# I2C.net
KiCad netlist of a schematic drawn in EAGLE
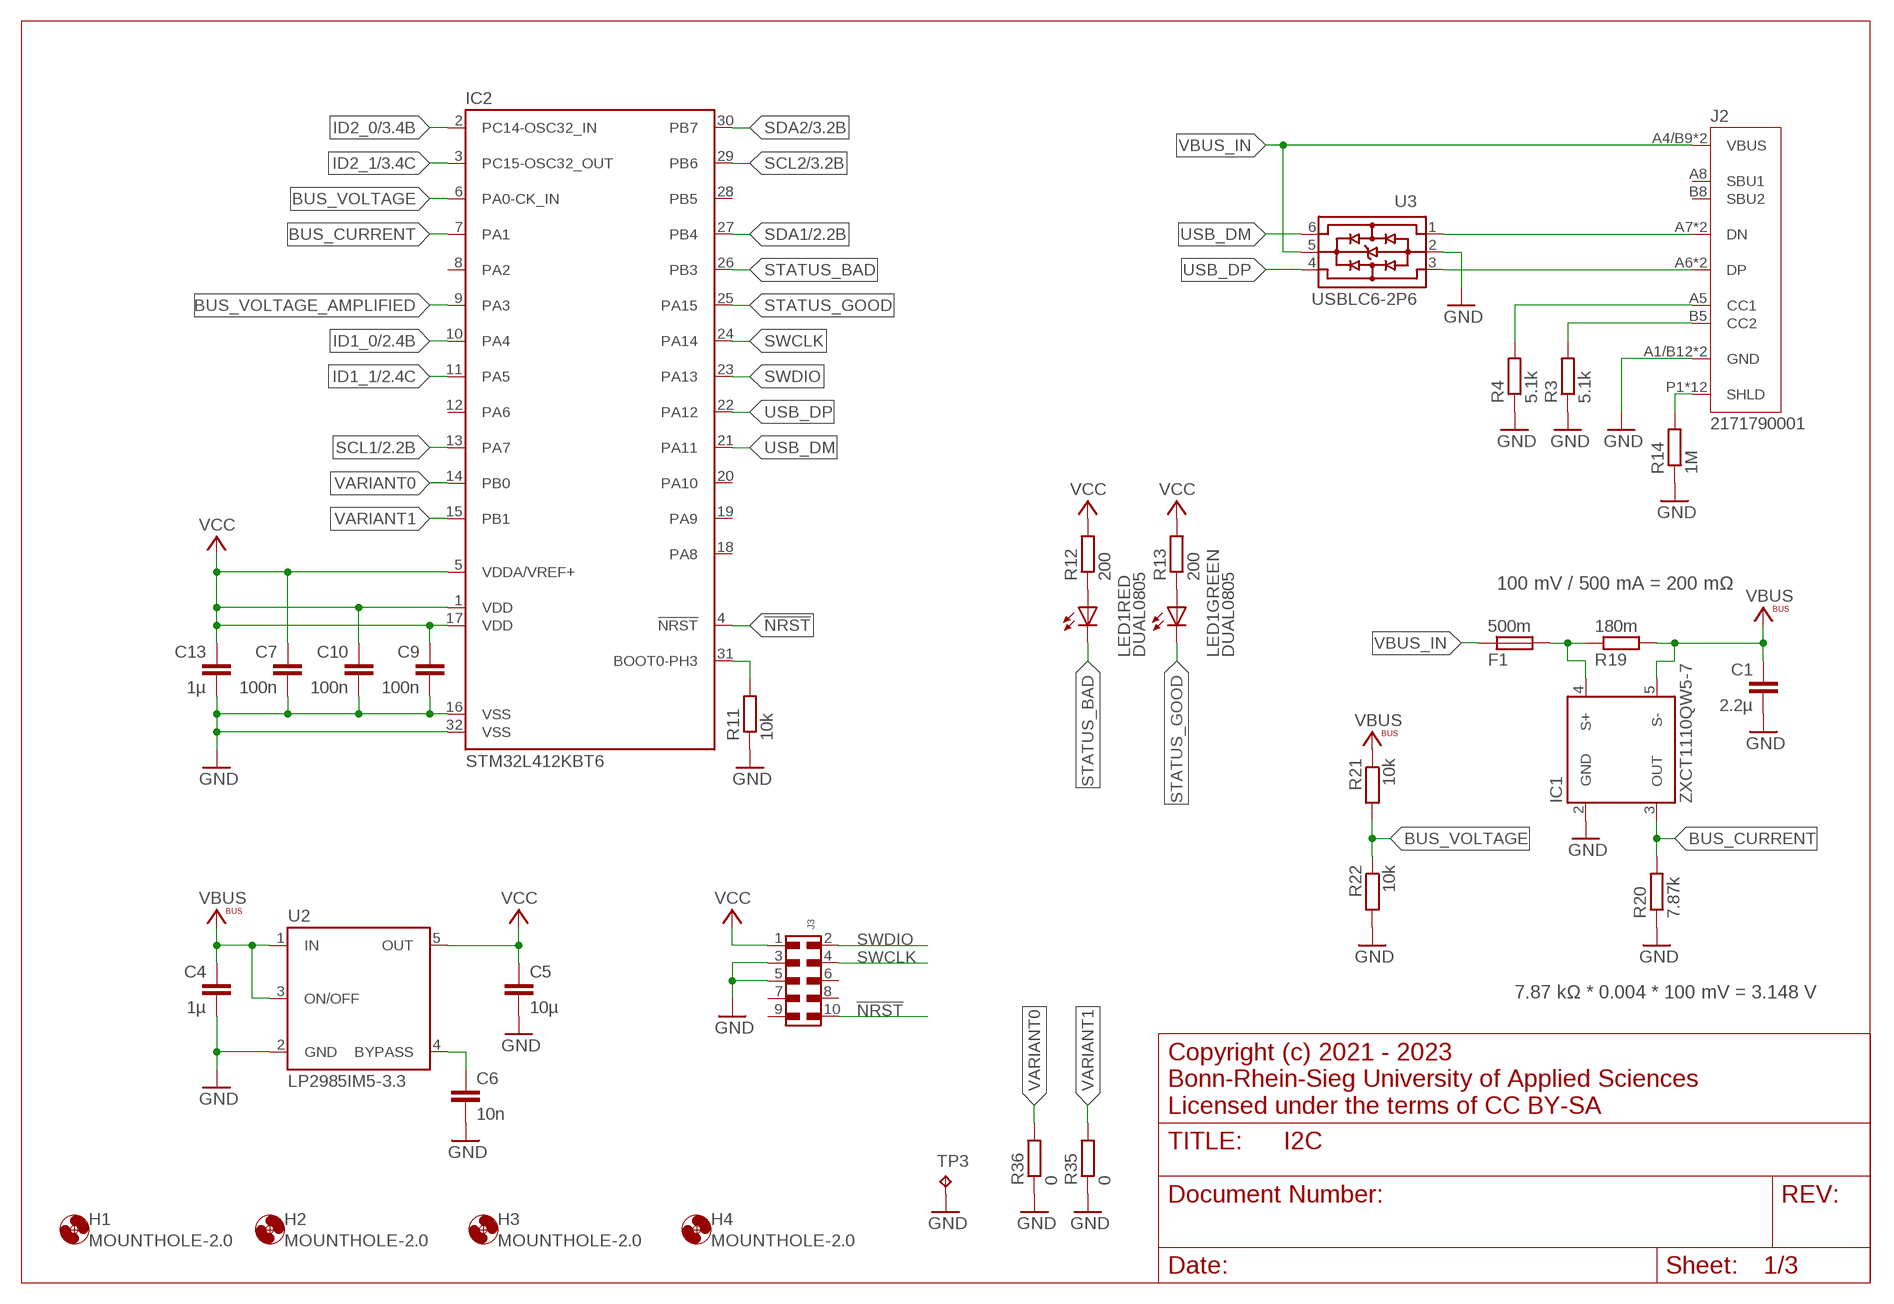
[diagram p0: schematic, sheet 1]
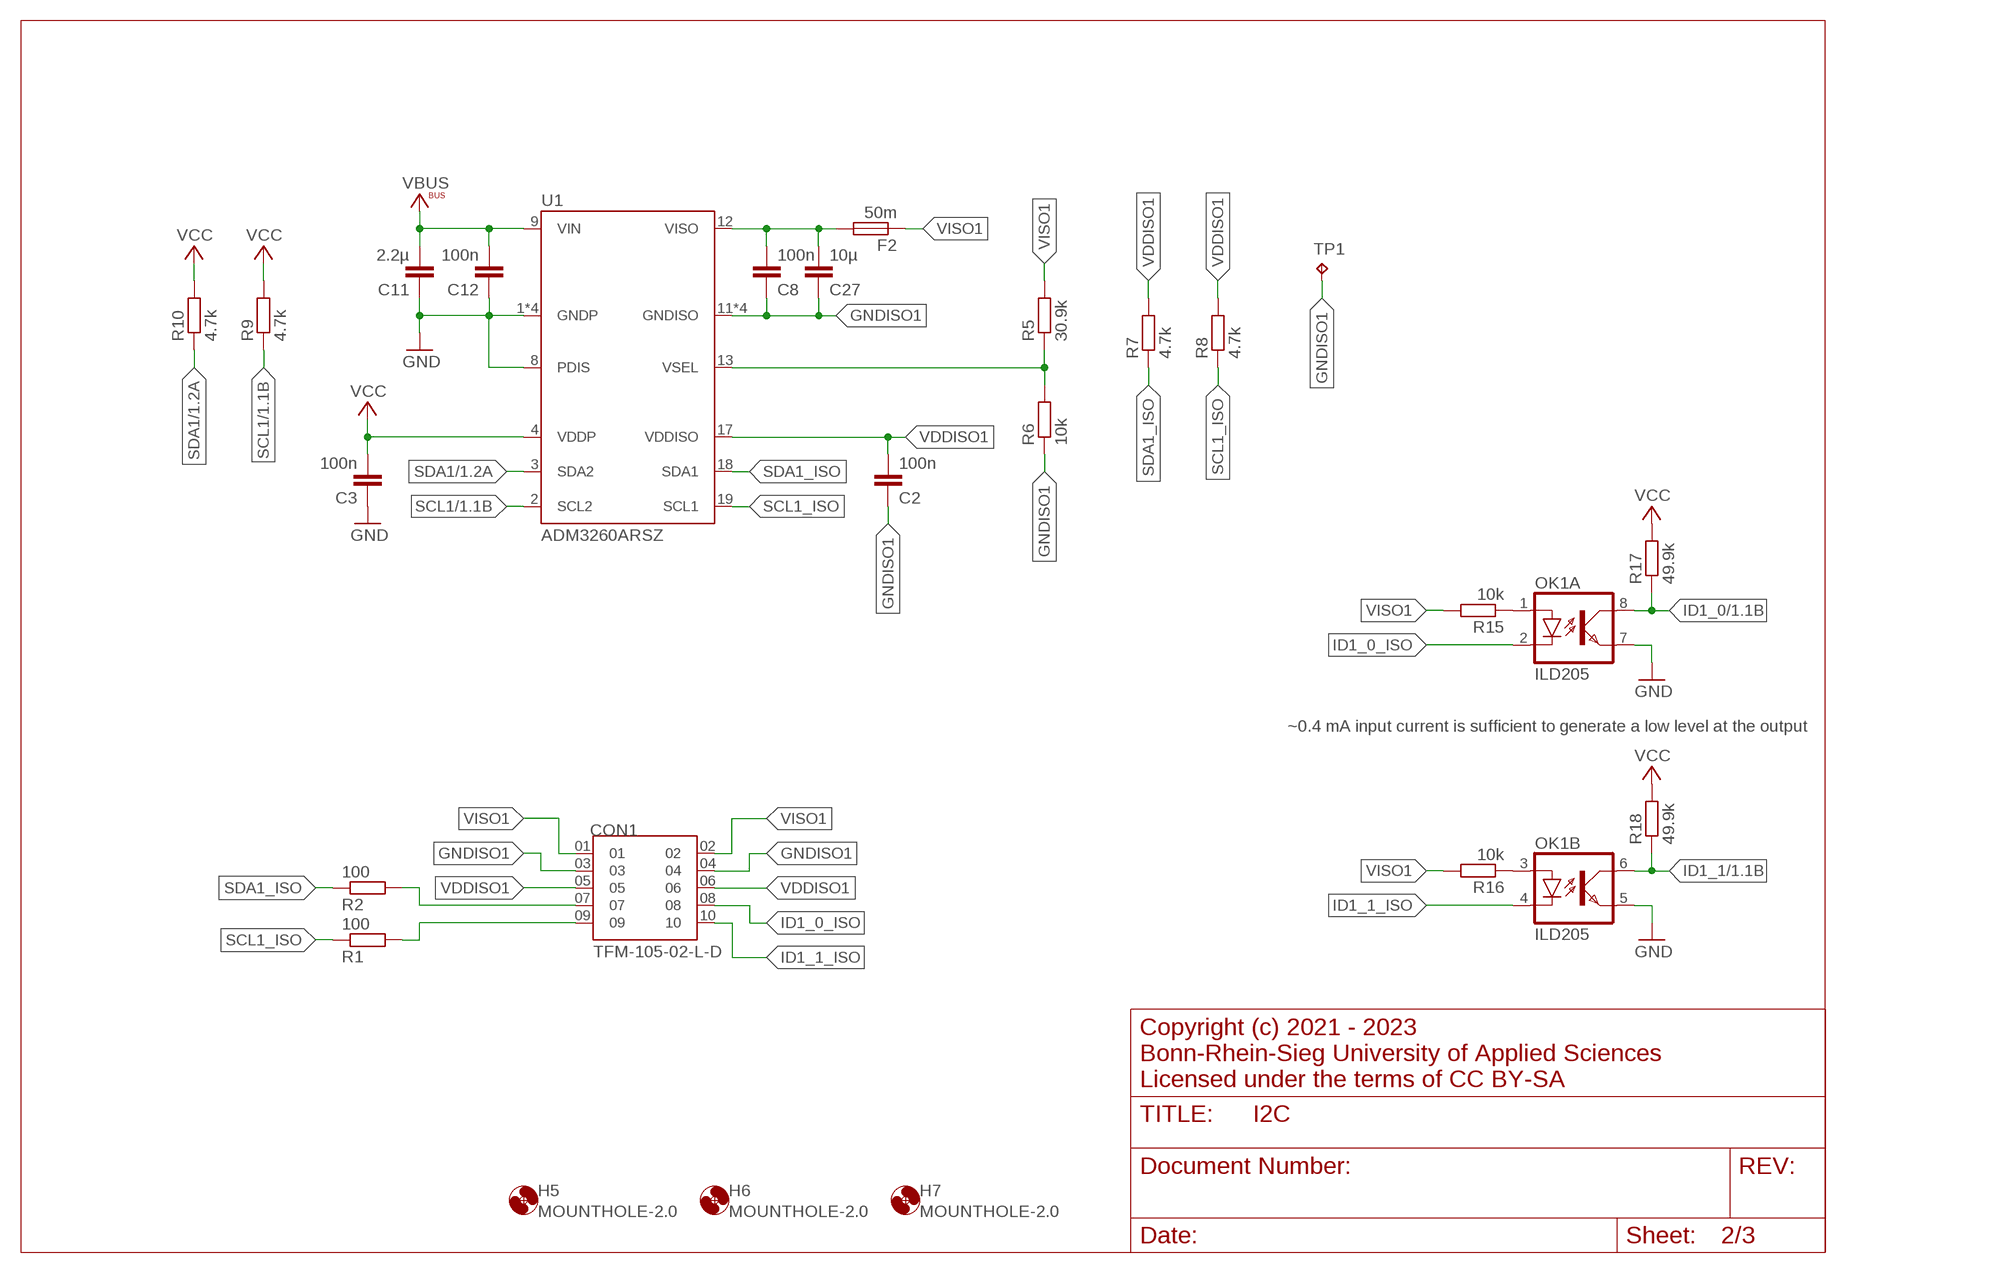
[diagram p1: schematic, sheet 2]
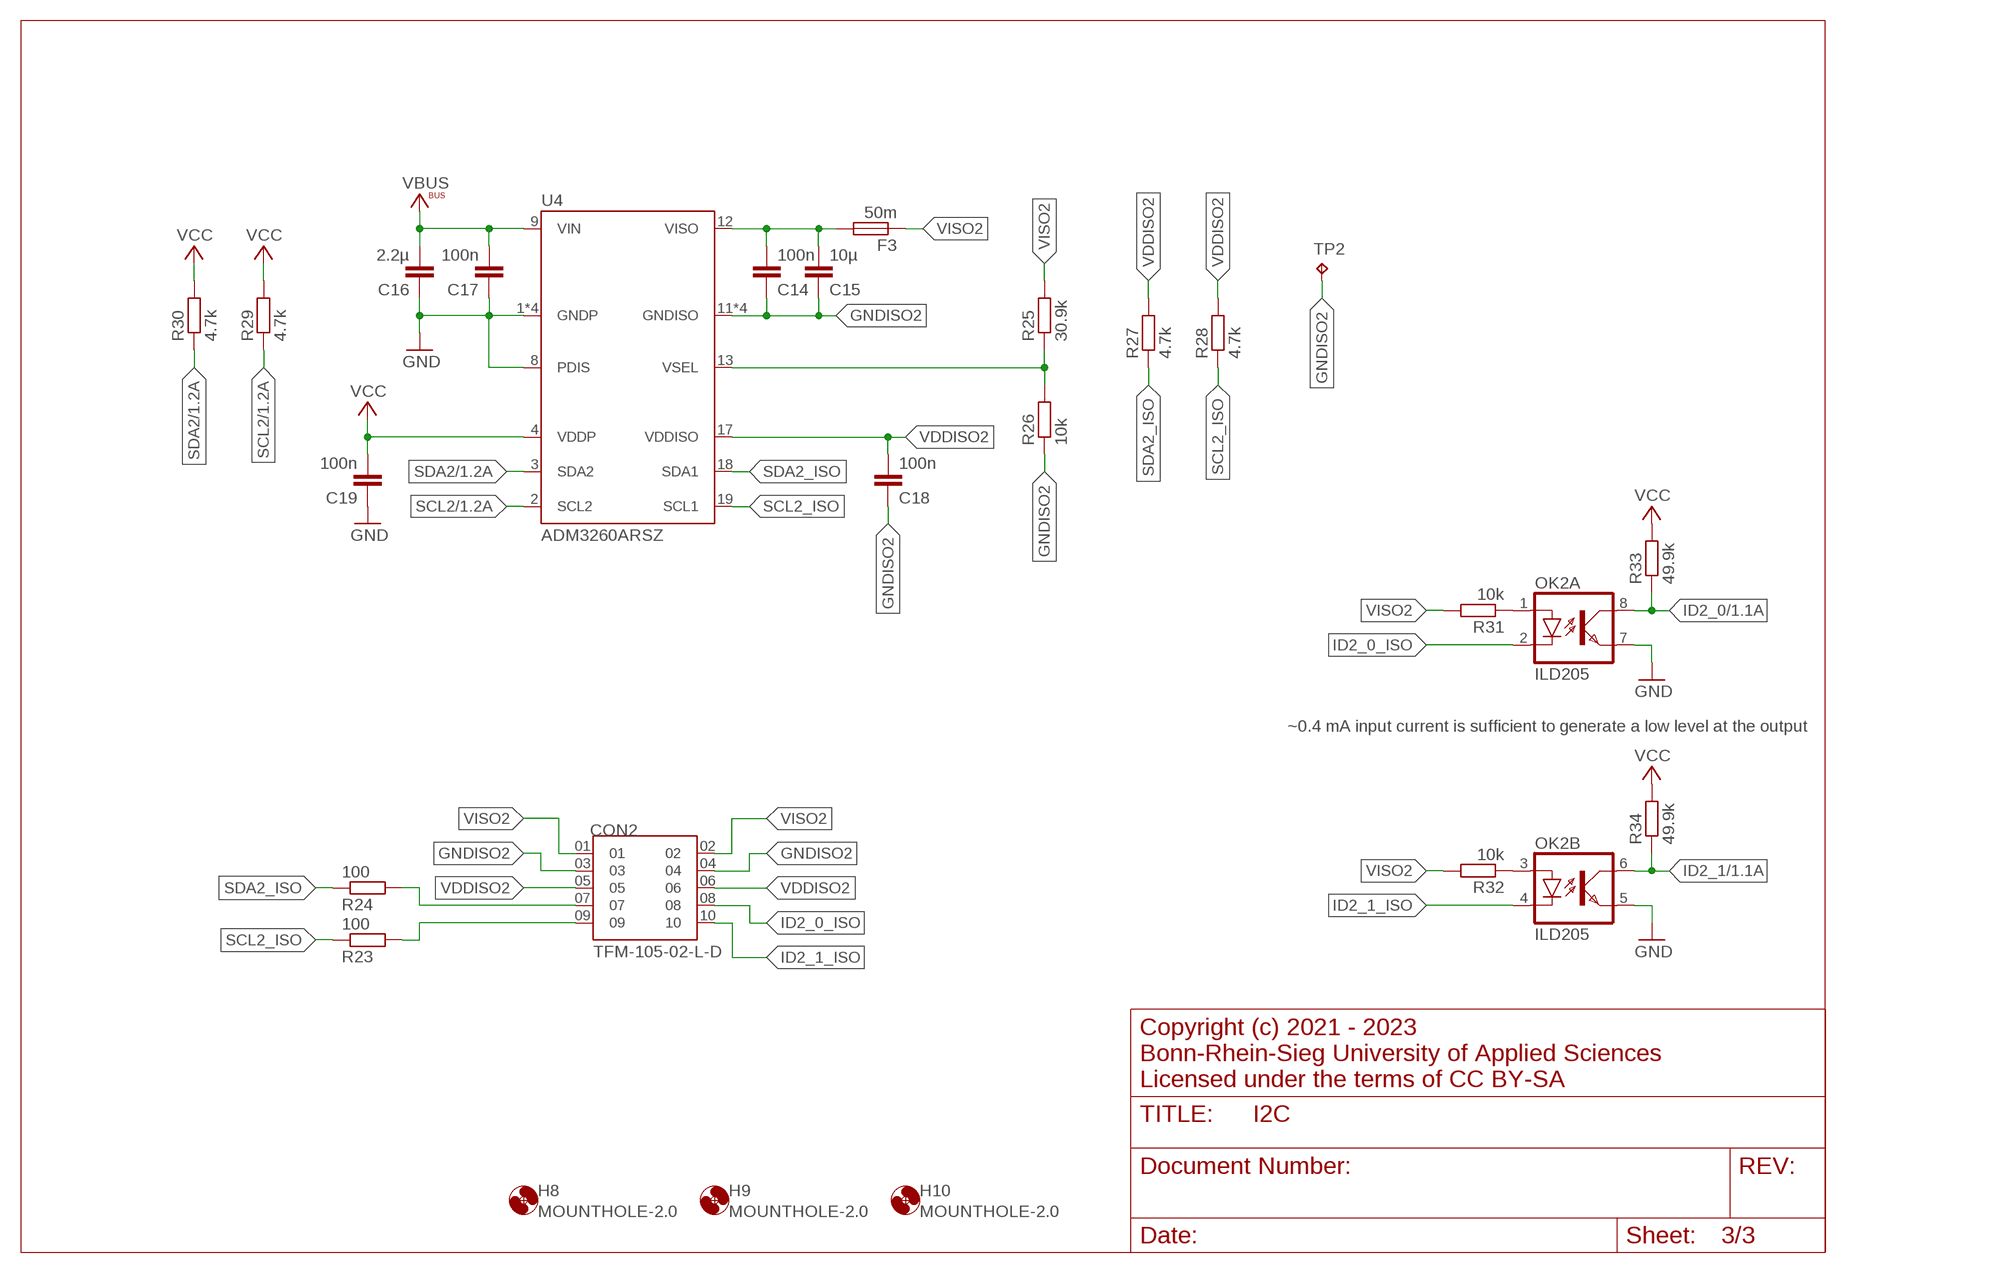
[diagram p2: schematic, sheet 3]

(export (version "E")
  (design (tool "Eeschema 10.0.6"))
  (components
    (comp (ref "C2")
      (value "100n")
      (footprint "eagle-import:C0603")
      (libsource (lib "eagle-import") (part "C-EUC0603"))
    )
    (comp (ref "C3")
      (value "100n")
      (footprint "eagle-import:C0603")
      (libsource (lib "eagle-import") (part "C-EUC0603"))
    )
    (comp (ref "C8")
      (value "100n")
      (footprint "eagle-import:C0603")
      (libsource (lib "eagle-import") (part "C-EUC0603"))
    )
    (comp (ref "C11")
      (value "2.2µ")
      (footprint "eagle-import:C0603")
      (libsource (lib "eagle-import") (part "C-EUC0603"))
    )
    (comp (ref "C12")
      (value "100n")
      (footprint "eagle-import:C0603")
      (libsource (lib "eagle-import") (part "C-EUC0603"))
    )
    (comp (ref "C27")
      (value "10µ")
      (footprint "eagle-import:C0603")
      (libsource (lib "eagle-import") (part "C-EUC0603"))
    )
    (comp (ref "CON1")
      (value "TFM-105-02-L-D")
      (footprint "eagle-import:SAMTEC_TFM-105-02-L-D")
      (libsource (lib "eagle-import") (part "TFM-105-02-L-D"))
    )
    (comp (ref "F2")
      (value "50m")
      (footprint "eagle-import:R0603")
      (libsource (lib "eagle-import") (part "FUSE0603"))
    )
    (comp (ref "H5")
      (value "MOUNTHOLE-2.0")
      (footprint "eagle-import:2.0")
      (libsource (lib "eagle-import") (part "MOUNTHOLE-2.0"))
    )
    (comp (ref "H6")
      (value "MOUNTHOLE-2.0")
      (footprint "eagle-import:2.0")
      (libsource (lib "eagle-import") (part "MOUNTHOLE-2.0"))
    )
    (comp (ref "H7")
      (value "MOUNTHOLE-2.0")
      (footprint "eagle-import:2.0")
      (libsource (lib "eagle-import") (part "MOUNTHOLE-2.0"))
    )
    (comp (ref "OK1")
      (value "ILD205")
      (footprint "eagle-import:SOIC08")
      (fields (field (name "MF") "VISHAY/TELEFUNKEN") (field (name "MPN") "ILD205T"))
      (libsource (lib "eagle-import") (part "ILD205"))
    )
    (comp (ref "R1")
      (value "100")
      (footprint "eagle-import:R0603")
      (libsource (lib "eagle-import") (part "rcl_334_R-EU_R0603"))
    )
    (comp (ref "R2")
      (value "100")
      (footprint "eagle-import:R0603")
      (libsource (lib "eagle-import") (part "rcl_334_R-EU_R0603"))
    )
    (comp (ref "R5")
      (value "30.9k")
      (footprint "eagle-import:R0603")
      (libsource (lib "eagle-import") (part "rcl_334_R-EU_R0603"))
    )
    (comp (ref "R6")
      (value "10k")
      (footprint "eagle-import:R0603")
      (libsource (lib "eagle-import") (part "rcl_334_R-EU_R0603"))
    )
    (comp (ref "R7")
      (value "4.7k")
      (footprint "eagle-import:R0603")
      (libsource (lib "eagle-import") (part "rcl_334_R-EU_R0603"))
    )
    (comp (ref "R8")
      (value "4.7k")
      (footprint "eagle-import:R0603")
      (libsource (lib "eagle-import") (part "rcl_334_R-EU_R0603"))
    )
    (comp (ref "R9")
      (value "4.7k")
      (footprint "eagle-import:R0603")
      (libsource (lib "eagle-import") (part "rcl_334_R-EU_R0603"))
    )
    (comp (ref "R10")
      (value "4.7k")
      (footprint "eagle-import:R0603")
      (libsource (lib "eagle-import") (part "rcl_334_R-EU_R0603"))
    )
    (comp (ref "R15")
      (value "10k")
      (footprint "eagle-import:R0603")
      (libsource (lib "eagle-import") (part "rcl_334_R-EU_R0603"))
    )
    (comp (ref "R16")
      (value "10k")
      (footprint "eagle-import:R0603")
      (libsource (lib "eagle-import") (part "rcl_334_R-EU_R0603"))
    )
    (comp (ref "R17")
      (value "49.9k")
      (footprint "eagle-import:R0603")
      (libsource (lib "eagle-import") (part "rcl_334_R-EU_R0603"))
    )
    (comp (ref "R18")
      (value "49.9k")
      (footprint "eagle-import:R0603")
      (libsource (lib "eagle-import") (part "rcl_334_R-EU_R0603"))
    )
    (comp (ref "TP1")
      (value "TP3.8X2.03")
      (footprint "eagle-import:3.8X2.03")
      (libsource (lib "eagle-import") (part "TP3.8X2.03"))
    )
    (comp (ref "U1")
      (value "ADM3260ARSZ")
      (footprint "eagle-import:SSOP20")
      (libsource (lib "eagle-import") (part "ADM3260RSZA"))
    )
    (comp (ref "C14")
      (value "100n")
      (footprint "eagle-import:C0603")
      (libsource (lib "eagle-import") (part "C-EUC0603"))
    )
    (comp (ref "C15")
      (value "10µ")
      (footprint "eagle-import:C0603")
      (libsource (lib "eagle-import") (part "C-EUC0603"))
    )
    (comp (ref "C16")
      (value "2.2µ")
      (footprint "eagle-import:C0603")
      (libsource (lib "eagle-import") (part "C-EUC0603"))
    )
    (comp (ref "C17")
      (value "100n")
      (footprint "eagle-import:C0603")
      (libsource (lib "eagle-import") (part "C-EUC0603"))
    )
    (comp (ref "C18")
      (value "100n")
      (footprint "eagle-import:C0603")
      (libsource (lib "eagle-import") (part "C-EUC0603"))
    )
    (comp (ref "C19")
      (value "100n")
      (footprint "eagle-import:C0603")
      (libsource (lib "eagle-import") (part "C-EUC0603"))
    )
    (comp (ref "CON2")
      (value "TFM-105-02-L-D")
      (footprint "eagle-import:SAMTEC_TFM-105-02-L-D")
      (libsource (lib "eagle-import") (part "TFM-105-02-L-D"))
    )
    (comp (ref "F3")
      (value "50m")
      (footprint "eagle-import:R0603")
      (libsource (lib "eagle-import") (part "FUSE0603"))
    )
    (comp (ref "H8")
      (value "MOUNTHOLE-2.0")
      (footprint "eagle-import:2.0")
      (libsource (lib "eagle-import") (part "MOUNTHOLE-2.0"))
    )
    (comp (ref "H9")
      (value "MOUNTHOLE-2.0")
      (footprint "eagle-import:2.0")
      (libsource (lib "eagle-import") (part "MOUNTHOLE-2.0"))
    )
    (comp (ref "H10")
      (value "MOUNTHOLE-2.0")
      (footprint "eagle-import:2.0")
      (libsource (lib "eagle-import") (part "MOUNTHOLE-2.0"))
    )
    (comp (ref "OK2")
      (value "ILD205")
      (footprint "eagle-import:SOIC08")
      (fields (field (name "MF") "VISHAY/TELEFUNKEN") (field (name "MPN") "ILD205T"))
      (libsource (lib "eagle-import") (part "ILD205"))
    )
    (comp (ref "R23")
      (value "100")
      (footprint "eagle-import:R0603")
      (libsource (lib "eagle-import") (part "rcl_334_R-EU_R0603"))
    )
    (comp (ref "R24")
      (value "100")
      (footprint "eagle-import:R0603")
      (libsource (lib "eagle-import") (part "rcl_334_R-EU_R0603"))
    )
    (comp (ref "R25")
      (value "30.9k")
      (footprint "eagle-import:R0603")
      (libsource (lib "eagle-import") (part "rcl_334_R-EU_R0603"))
    )
    (comp (ref "R26")
      (value "10k")
      (footprint "eagle-import:R0603")
      (libsource (lib "eagle-import") (part "rcl_334_R-EU_R0603"))
    )
    (comp (ref "R27")
      (value "4.7k")
      (footprint "eagle-import:R0603")
      (libsource (lib "eagle-import") (part "rcl_334_R-EU_R0603"))
    )
    (comp (ref "R28")
      (value "4.7k")
      (footprint "eagle-import:R0603")
      (libsource (lib "eagle-import") (part "rcl_334_R-EU_R0603"))
    )
    (comp (ref "R29")
      (value "4.7k")
      (footprint "eagle-import:R0603")
      (libsource (lib "eagle-import") (part "rcl_334_R-EU_R0603"))
    )
    (comp (ref "R30")
      (value "4.7k")
      (footprint "eagle-import:R0603")
      (libsource (lib "eagle-import") (part "rcl_334_R-EU_R0603"))
    )
    (comp (ref "R31")
      (value "10k")
      (footprint "eagle-import:R0603")
      (libsource (lib "eagle-import") (part "rcl_334_R-EU_R0603"))
    )
    (comp (ref "R32")
      (value "10k")
      (footprint "eagle-import:R0603")
      (libsource (lib "eagle-import") (part "rcl_334_R-EU_R0603"))
    )
    (comp (ref "R33")
      (value "49.9k")
      (footprint "eagle-import:R0603")
      (libsource (lib "eagle-import") (part "rcl_334_R-EU_R0603"))
    )
    (comp (ref "R34")
      (value "49.9k")
      (footprint "eagle-import:R0603")
      (libsource (lib "eagle-import") (part "rcl_334_R-EU_R0603"))
    )
    (comp (ref "TP2")
      (value "TP3.8X2.03")
      (footprint "eagle-import:3.8X2.03")
      (libsource (lib "eagle-import") (part "TP3.8X2.03"))
    )
    (comp (ref "U4")
      (value "ADM3260ARSZ")
      (footprint "eagle-import:SSOP20")
      (libsource (lib "eagle-import") (part "ADM3260RSZA"))
    )
    (comp (ref "C1")
      (value "2.2µ")
      (footprint "eagle-import:C0805")
      (libsource (lib "eagle-import") (part "rcl_334_C-EUC0805"))
    )
    (comp (ref "C4")
      (value "1µ")
      (footprint "eagle-import:C0805")
      (libsource (lib "eagle-import") (part "rcl_334_C-EUC0805"))
    )
    (comp (ref "C5")
      (value "10µ")
      (footprint "eagle-import:C0603")
      (libsource (lib "eagle-import") (part "rcl_334_C-EUC0603"))
    )
    (comp (ref "C6")
      (value "10n")
      (footprint "eagle-import:C0603")
      (libsource (lib "eagle-import") (part "rcl_334_C-EUC0603"))
    )
    (comp (ref "C7")
      (value "100n")
      (footprint "eagle-import:C0603")
      (libsource (lib "eagle-import") (part "C-EUC0603"))
    )
    (comp (ref "C9")
      (value "100n")
      (footprint "eagle-import:C0603")
      (libsource (lib "eagle-import") (part "C-EUC0603"))
    )
    (comp (ref "C10")
      (value "100n")
      (footprint "eagle-import:C0603")
      (libsource (lib "eagle-import") (part "C-EUC0603"))
    )
    (comp (ref "C13")
      (value "1µ")
      (footprint "eagle-import:C0603")
      (libsource (lib "eagle-import") (part "C-EUC0603"))
    )
    (comp (ref "F1")
      (value "500m")
      (footprint "eagle-import:R0603")
      (libsource (lib "eagle-import") (part "FUSE0603"))
    )
    (comp (ref "H1")
      (value "MOUNTHOLE-2.0")
      (footprint "eagle-import:2.0")
      (libsource (lib "eagle-import") (part "MOUNTHOLE-2.0"))
    )
    (comp (ref "H2")
      (value "MOUNTHOLE-2.0")
      (footprint "eagle-import:2.0")
      (libsource (lib "eagle-import") (part "MOUNTHOLE-2.0"))
    )
    (comp (ref "H3")
      (value "MOUNTHOLE-2.0")
      (footprint "eagle-import:2.0")
      (libsource (lib "eagle-import") (part "MOUNTHOLE-2.0"))
    )
    (comp (ref "H4")
      (value "MOUNTHOLE-2.0")
      (footprint "eagle-import:2.0")
      (libsource (lib "eagle-import") (part "MOUNTHOLE-2.0"))
    )
    (comp (ref "IC1")
      (value "ZXCT1110QW5-7")
      (footprint "eagle-import:SOT23-5L")
      (libsource (lib "eagle-import") (part "ZXCT1110QW5-7"))
    )
    (comp (ref "IC2")
      (value "STM32L412KBT6")
      (footprint "eagle-import:LQFP32")
      (libsource (lib "eagle-import") (part "STM32L412K?T6B"))
    )
    (comp (ref "J2")
      (value "2171790001")
      (footprint "eagle-import:2171790001_MOL")
      (fields (field (name "COPYRIGHT") "Copyright (C) 2021 Ultra Librarian. All rights reserved."))
      (libsource (lib "eagle-import") (part "2171790001"))
    )
    (comp (ref "J3")
      (value "6210XX21021_62101021021")
      (footprint "eagle-import:62101021021")
      (libsource (lib "eagle-import") (part "6210XX21021_62101021021"))
    )
    (comp (ref "LED1")
      (value "DUAL0805")
      (footprint "eagle-import:CHIPLEDX2")
      (libsource (lib "eagle-import") (part "DUAL0805"))
    )
    (comp (ref "R3")
      (value "5.1k")
      (footprint "eagle-import:R0603")
      (libsource (lib "eagle-import") (part "rcl_334_R-EU_R0603"))
    )
    (comp (ref "R4")
      (value "5.1k")
      (footprint "eagle-import:R0603")
      (libsource (lib "eagle-import") (part "rcl_334_R-EU_R0603"))
    )
    (comp (ref "R11")
      (value "10k")
      (footprint "eagle-import:R0603")
      (libsource (lib "eagle-import") (part "rcl_334_R-EU_R0603"))
    )
    (comp (ref "R12")
      (value "200")
      (footprint "eagle-import:R0603")
      (libsource (lib "eagle-import") (part "rcl_334_R-EU_R0603"))
    )
    (comp (ref "R13")
      (value "200")
      (footprint "eagle-import:R0603")
      (libsource (lib "eagle-import") (part "rcl_334_R-EU_R0603"))
    )
    (comp (ref "R14")
      (value "1M")
      (footprint "eagle-import:R0603")
      (libsource (lib "eagle-import") (part "rcl_334_R-EU_R0603"))
    )
    (comp (ref "R19")
      (value "180m")
      (footprint "eagle-import:R0805")
      (libsource (lib "eagle-import") (part "rcl_334_R-EU_R0805"))
    )
    (comp (ref "R20")
      (value "7.87k")
      (footprint "eagle-import:R0603")
      (libsource (lib "eagle-import") (part "rcl_334_R-EU_R0603"))
    )
    (comp (ref "R21")
      (value "10k")
      (footprint "eagle-import:R0603")
      (libsource (lib "eagle-import") (part "rcl_334_R-EU_R0603"))
    )
    (comp (ref "R22")
      (value "10k")
      (footprint "eagle-import:R0603")
      (libsource (lib "eagle-import") (part "rcl_334_R-EU_R0603"))
    )
    (comp (ref "R35")
      (value "0")
      (footprint "eagle-import:R0603")
      (libsource (lib "eagle-import") (part "R-EU_R0603"))
    )
    (comp (ref "R36")
      (value "0")
      (footprint "eagle-import:R0603")
      (libsource (lib "eagle-import") (part "R-EU_R0603"))
    )
    (comp (ref "TP3")
      (value "TP3.8X2.03")
      (footprint "eagle-import:3.8X2.03")
      (libsource (lib "eagle-import") (part "TP3.8X2.03"))
    )
    (comp (ref "U2")
      (value "LP2985IM5-3.3")
      (footprint "eagle-import:SOT23-5")
      (libsource (lib "eagle-import") (part "LP2985?-IM53.3"))
    )
    (comp (ref "U3")
      (value "USBLC6-2P6")
      (footprint "eagle-import:SOT-666")
      (libsource (lib "eagle-import") (part "USBLC6-2P6"))
    )
  )
  (nets
    (net (code "1") (name "BUS_CURRENT") (class "Default")
      (node (ref "IC1") (pin "3") (pinfunction "OUT_3") (pintype "output"))
      (node (ref "IC2") (pin "7") (pinfunction "PA1_7") (pintype "bidirectional"))
      (node (ref "R20") (pin "2") (pinfunction "2_2") (pintype "passive"))
    )
    (net (code "2") (name "BUS_VOLTAGE") (class "Default")
      (node (ref "IC2") (pin "6") (pinfunction "PA0-CK_IN_6") (pintype "bidirectional"))
      (node (ref "R21") (pin "2") (pinfunction "2_2") (pintype "passive"))
      (node (ref "R22") (pin "1") (pinfunction "1_1") (pintype "passive"))
    )
    (net (code "3") (name "BUS_VOLTAGE_AMPLIFIED") (class "Default")
      (node (ref "IC2") (pin "9") (pinfunction "PA3_9") (pintype "bidirectional"))
    )
    (net (code "4") (name "GND") (class "Default")
      (node (ref "C1") (pin "2") (pinfunction "2_2") (pintype "passive"))
      (node (ref "C10") (pin "2") (pinfunction "2_2") (pintype "passive"))
      (node (ref "C11") (pin "1") (pinfunction "1_1") (pintype "passive"))
      (node (ref "C12") (pin "1") (pinfunction "1_1") (pintype "passive"))
      (node (ref "C13") (pin "2") (pinfunction "2_2") (pintype "passive"))
      (node (ref "C16") (pin "1") (pinfunction "1_1") (pintype "passive"))
      (node (ref "C17") (pin "1") (pinfunction "1_1") (pintype "passive"))
      (node (ref "C19") (pin "1") (pinfunction "1_1") (pintype "passive"))
      (node (ref "C3") (pin "1") (pinfunction "1_1") (pintype "passive"))
      (node (ref "C4") (pin "2") (pinfunction "2_2") (pintype "passive"))
      (node (ref "C5") (pin "2") (pinfunction "2_2") (pintype "passive"))
      (node (ref "C6") (pin "2") (pinfunction "2_2") (pintype "passive"))
      (node (ref "C7") (pin "2") (pinfunction "2_2") (pintype "passive"))
      (node (ref "C9") (pin "2") (pinfunction "2_2") (pintype "passive"))
      (node (ref "IC1") (pin "2") (pinfunction "GND_2") (pintype "power_in"))
      (node (ref "IC2") (pin "16") (pinfunction "VSS_16") (pintype "bidirectional"))
      (node (ref "IC2") (pin "32") (pinfunction "VSS_32") (pintype "bidirectional"))
      (node (ref "J2") (pin "A1/B12") (pinfunction "GND_A1/B12") (pintype "passive"))
      (node (ref "J2") (pin "B1/A12") (pinfunction "GND_B1/A12") (pintype "passive"))
      (node (ref "J3") (pin "3") (pinfunction "3_3") (pintype "passive"))
      (node (ref "J3") (pin "5") (pinfunction "5_5") (pintype "passive"))
      (node (ref "OK1") (pin "5") (pinfunction "EMIT_5") (pintype "passive"))
      (node (ref "OK1") (pin "7") (pinfunction "EMIT_7") (pintype "passive"))
      (node (ref "OK2") (pin "5") (pinfunction "EMIT_5") (pintype "passive"))
      (node (ref "OK2") (pin "7") (pinfunction "EMIT_7") (pintype "passive"))
      (node (ref "R11") (pin "1") (pinfunction "1_1") (pintype "passive"))
      (node (ref "R14") (pin "1") (pinfunction "1_1") (pintype "passive"))
      (node (ref "R20") (pin "1") (pinfunction "1_1") (pintype "passive"))
      (node (ref "R22") (pin "2") (pinfunction "2_2") (pintype "passive"))
      (node (ref "R3") (pin "1") (pinfunction "1_1") (pintype "passive"))
      (node (ref "R35") (pin "1") (pinfunction "1_1") (pintype "passive"))
      (node (ref "R36") (pin "1") (pinfunction "1_1") (pintype "passive"))
      (node (ref "R4") (pin "1") (pinfunction "1_1") (pintype "passive"))
      (node (ref "TP3") (pin "TP") (pinfunction "TP_TP") (pintype "input"))
      (node (ref "U1") (pin "1") (pinfunction "GNDP_1") (pintype "bidirectional"))
      (node (ref "U1") (pin "10") (pinfunction "GNDP_10") (pintype "bidirectional"))
      (node (ref "U1") (pin "5") (pinfunction "GNDP_5") (pintype "bidirectional"))
      (node (ref "U1") (pin "7") (pinfunction "GNDP_7") (pintype "bidirectional"))
      (node (ref "U1") (pin "8") (pinfunction "PDIS_8") (pintype "bidirectional"))
      (node (ref "U2") (pin "2") (pinfunction "GND_2") (pintype "bidirectional"))
      (node (ref "U3") (pin "2") (pinfunction "2_2") (pintype "passive"))
      (node (ref "U4") (pin "1") (pinfunction "GNDP_1") (pintype "bidirectional"))
      (node (ref "U4") (pin "10") (pinfunction "GNDP_10") (pintype "bidirectional"))
      (node (ref "U4") (pin "5") (pinfunction "GNDP_5") (pintype "bidirectional"))
      (node (ref "U4") (pin "7") (pinfunction "GNDP_7") (pintype "bidirectional"))
      (node (ref "U4") (pin "8") (pinfunction "PDIS_8") (pintype "bidirectional"))
    )
    (net (code "5") (name "GNDISO1") (class "Default")
      (node (ref "C2") (pin "1") (pinfunction "1_1") (pintype "passive"))
      (node (ref "C27") (pin "1") (pinfunction "1_1") (pintype "passive"))
      (node (ref "C8") (pin "1") (pinfunction "1_1") (pintype "passive"))
      (node (ref "CON1") (pin "03") (pinfunction "03_03") (pintype "passive"))
      (node (ref "CON1") (pin "04") (pinfunction "04_04") (pintype "passive"))
      (node (ref "R6") (pin "1") (pinfunction "1_1") (pintype "passive"))
      (node (ref "TP1") (pin "TP") (pinfunction "TP_TP") (pintype "input"))
      (node (ref "U1") (pin "11") (pinfunction "GNDISO_11") (pintype "bidirectional"))
      (node (ref "U1") (pin "14") (pinfunction "GNDISO_14") (pintype "bidirectional"))
      (node (ref "U1") (pin "16") (pinfunction "GNDISO_16") (pintype "bidirectional"))
      (node (ref "U1") (pin "20") (pinfunction "GNDISO_20") (pintype "bidirectional"))
    )
    (net (code "6") (name "GNDISO2") (class "Default")
      (node (ref "C14") (pin "1") (pinfunction "1_1") (pintype "passive"))
      (node (ref "C15") (pin "1") (pinfunction "1_1") (pintype "passive"))
      (node (ref "C18") (pin "1") (pinfunction "1_1") (pintype "passive"))
      (node (ref "CON2") (pin "03") (pinfunction "03_03") (pintype "passive"))
      (node (ref "CON2") (pin "04") (pinfunction "04_04") (pintype "passive"))
      (node (ref "R26") (pin "1") (pinfunction "1_1") (pintype "passive"))
      (node (ref "TP2") (pin "TP") (pinfunction "TP_TP") (pintype "input"))
      (node (ref "U4") (pin "11") (pinfunction "GNDISO_11") (pintype "bidirectional"))
      (node (ref "U4") (pin "14") (pinfunction "GNDISO_14") (pintype "bidirectional"))
      (node (ref "U4") (pin "16") (pinfunction "GNDISO_16") (pintype "bidirectional"))
      (node (ref "U4") (pin "20") (pinfunction "GNDISO_20") (pintype "bidirectional"))
    )
    (net (code "7") (name "ID1_0") (class "Default")
      (node (ref "IC2") (pin "10") (pinfunction "PA4_10") (pintype "bidirectional"))
      (node (ref "OK1") (pin "8") (pinfunction "COL_8") (pintype "passive"))
      (node (ref "R17") (pin "1") (pinfunction "1_1") (pintype "passive"))
    )
    (net (code "8") (name "ID1_0_ISO") (class "Default")
      (node (ref "CON1") (pin "08") (pinfunction "08_08") (pintype "passive"))
      (node (ref "OK1") (pin "2") (pinfunction "C_2") (pintype "passive"))
    )
    (net (code "9") (name "ID1_1") (class "Default")
      (node (ref "IC2") (pin "11") (pinfunction "PA5_11") (pintype "bidirectional"))
      (node (ref "OK1") (pin "6") (pinfunction "COL_6") (pintype "passive"))
      (node (ref "R18") (pin "1") (pinfunction "1_1") (pintype "passive"))
    )
    (net (code "10") (name "ID1_1_ISO") (class "Default")
      (node (ref "CON1") (pin "10") (pinfunction "10_10") (pintype "passive"))
      (node (ref "OK1") (pin "4") (pinfunction "C_4") (pintype "passive"))
    )
    (net (code "11") (name "ID2_0") (class "Default")
      (node (ref "IC2") (pin "2") (pinfunction "PC14-OSC32_IN_2") (pintype "bidirectional"))
      (node (ref "OK2") (pin "8") (pinfunction "COL_8") (pintype "passive"))
      (node (ref "R33") (pin "1") (pinfunction "1_1") (pintype "passive"))
    )
    (net (code "12") (name "ID2_0_ISO") (class "Default")
      (node (ref "CON2") (pin "08") (pinfunction "08_08") (pintype "passive"))
      (node (ref "OK2") (pin "2") (pinfunction "C_2") (pintype "passive"))
    )
    (net (code "13") (name "ID2_1") (class "Default")
      (node (ref "IC2") (pin "3") (pinfunction "PC15-OSC32_OUT_3") (pintype "bidirectional"))
      (node (ref "OK2") (pin "6") (pinfunction "COL_6") (pintype "passive"))
      (node (ref "R34") (pin "1") (pinfunction "1_1") (pintype "passive"))
    )
    (net (code "14") (name "ID2_1_ISO") (class "Default")
      (node (ref "CON2") (pin "10") (pinfunction "10_10") (pintype "passive"))
      (node (ref "OK2") (pin "4") (pinfunction "C_4") (pintype "passive"))
    )
    (net (code "15") (name "Net-(CON1-Pad07)") (class "Default")
      (node (ref "CON1") (pin "07") (pinfunction "07_07") (pintype "passive"))
      (node (ref "R2") (pin "2") (pinfunction "2_2") (pintype "passive"))
    )
    (net (code "16") (name "Net-(CON1-Pad09)") (class "Default")
      (node (ref "CON1") (pin "09") (pinfunction "09_09") (pintype "passive"))
      (node (ref "R1") (pin "2") (pinfunction "2_2") (pintype "passive"))
    )
    (net (code "17") (name "Net-(CON2-Pad07)") (class "Default")
      (node (ref "CON2") (pin "07") (pinfunction "07_07") (pintype "passive"))
      (node (ref "R24") (pin "2") (pinfunction "2_2") (pintype "passive"))
    )
    (net (code "18") (name "Net-(CON2-Pad09)") (class "Default")
      (node (ref "CON2") (pin "09") (pinfunction "09_09") (pintype "passive"))
      (node (ref "R23") (pin "2") (pinfunction "2_2") (pintype "passive"))
    )
    (net (code "19") (name "Net-(IC1-S+)") (class "Default")
      (node (ref "F1") (pin "2") (pinfunction "2_2") (pintype "passive"))
      (node (ref "IC1") (pin "4") (pinfunction "S+_4") (pintype "input"))
      (node (ref "R19") (pin "1") (pinfunction "1_1") (pintype "passive"))
    )
    (net (code "20") (name "Net-(IC2-BOOT0-PH3)") (class "Default")
      (node (ref "IC2") (pin "31") (pinfunction "BOOT0-PH3_31") (pintype "bidirectional"))
      (node (ref "R11") (pin "2") (pinfunction "2_2") (pintype "passive"))
    )
    (net (code "21") (name "Net-(J2-CC1)") (class "Default")
      (node (ref "J2") (pin "A5") (pinfunction "CC1_A5") (pintype "bidirectional"))
      (node (ref "R4") (pin "2") (pinfunction "2_2") (pintype "passive"))
    )
    (net (code "22") (name "Net-(J2-CC2)") (class "Default")
      (node (ref "J2") (pin "B5") (pinfunction "CC2_B5") (pintype "bidirectional"))
      (node (ref "R3") (pin "2") (pinfunction "2_2") (pintype "passive"))
    )
    (net (code "23") (name "Net-(J2-DN-PadA7)") (class "Default")
      (node (ref "J2") (pin "A7") (pinfunction "DN_A7") (pintype "bidirectional"))
      (node (ref "J2") (pin "B7") (pinfunction "DN_B7") (pintype "bidirectional"))
      (node (ref "U3") (pin "1") (pinfunction "1_1") (pintype "bidirectional"))
    )
    (net (code "24") (name "Net-(J2-DP-PadA6)") (class "Default")
      (node (ref "J2") (pin "A6") (pinfunction "DP_A6") (pintype "bidirectional"))
      (node (ref "J2") (pin "B6") (pinfunction "DP_B6") (pintype "bidirectional"))
      (node (ref "U3") (pin "3") (pinfunction "3_3") (pintype "bidirectional"))
    )
    (net (code "25") (name "Net-(J2-SHLD-PadP1)") (class "Default")
      (node (ref "J2") (pin "P1") (pinfunction "SHLD_P1") (pintype "bidirectional"))
      (node (ref "J2") (pin "P2") (pinfunction "SHLD_P2") (pintype "bidirectional"))
      (node (ref "J2") (pin "P3") (pinfunction "SHLD_P3") (pintype "bidirectional"))
      (node (ref "J2") (pin "P4") (pinfunction "SHLD_P4") (pintype "bidirectional"))
      (node (ref "J2") (pin "S1") (pinfunction "SHLD_S1") (pintype "bidirectional"))
      (node (ref "J2") (pin "S2") (pinfunction "SHLD_S2") (pintype "bidirectional"))
      (node (ref "J2") (pin "S3") (pinfunction "SHLD_S3") (pintype "bidirectional"))
      (node (ref "J2") (pin "S4") (pinfunction "SHLD_S4") (pintype "bidirectional"))
      (node (ref "J2") (pin "S5") (pinfunction "SHLD_S5") (pintype "bidirectional"))
      (node (ref "J2") (pin "S6") (pinfunction "SHLD_S6") (pintype "bidirectional"))
      (node (ref "J2") (pin "S7") (pinfunction "SHLD_S7") (pintype "bidirectional"))
      (node (ref "J2") (pin "S8") (pinfunction "SHLD_S8") (pintype "bidirectional"))
      (node (ref "R14") (pin "2") (pinfunction "2_2") (pintype "passive"))
    )
    (net (code "26") (name "Net-(LED1A-A)") (class "Default")
      (node (ref "LED1") (pin "A2") (pinfunction "A_A2") (pintype "passive"))
      (node (ref "R13") (pin "1") (pinfunction "1_1") (pintype "passive"))
    )
    (net (code "27") (name "Net-(LED1B-A)") (class "Default")
      (node (ref "LED1") (pin "A1") (pinfunction "A_A1") (pintype "passive"))
      (node (ref "R12") (pin "1") (pinfunction "1_1") (pintype "passive"))
    )
    (net (code "28") (name "Net-(OK1A-A)") (class "Default")
      (node (ref "OK1") (pin "1") (pinfunction "A_1") (pintype "passive"))
      (node (ref "R15") (pin "1") (pinfunction "1_1") (pintype "passive"))
    )
    (net (code "29") (name "Net-(OK1B-A)") (class "Default")
      (node (ref "OK1") (pin "3") (pinfunction "A_3") (pintype "passive"))
      (node (ref "R16") (pin "1") (pinfunction "1_1") (pintype "passive"))
    )
    (net (code "30") (name "Net-(OK2A-A)") (class "Default")
      (node (ref "OK2") (pin "1") (pinfunction "A_1") (pintype "passive"))
      (node (ref "R31") (pin "1") (pinfunction "1_1") (pintype "passive"))
    )
    (net (code "31") (name "Net-(OK2B-A)") (class "Default")
      (node (ref "OK2") (pin "3") (pinfunction "A_3") (pintype "passive"))
      (node (ref "R32") (pin "1") (pinfunction "1_1") (pintype "passive"))
    )
    (net (code "32") (name "Net-(U1-VISO)") (class "Default")
      (node (ref "C27") (pin "2") (pinfunction "2_2") (pintype "passive"))
      (node (ref "C8") (pin "2") (pinfunction "2_2") (pintype "passive"))
      (node (ref "F2") (pin "2") (pinfunction "2_2") (pintype "passive"))
      (node (ref "U1") (pin "12") (pinfunction "VISO_12") (pintype "bidirectional"))
    )
    (net (code "33") (name "Net-(U1-VSEL)") (class "Default")
      (node (ref "R5") (pin "1") (pinfunction "1_1") (pintype "passive"))
      (node (ref "R6") (pin "2") (pinfunction "2_2") (pintype "passive"))
      (node (ref "U1") (pin "13") (pinfunction "VSEL_13") (pintype "bidirectional"))
    )
    (net (code "34") (name "Net-(U2-BYPASS)") (class "Default")
      (node (ref "C6") (pin "1") (pinfunction "1_1") (pintype "passive"))
      (node (ref "U2") (pin "4") (pinfunction "BYPASS_4") (pintype "bidirectional"))
    )
    (net (code "35") (name "Net-(U4-VISO)") (class "Default")
      (node (ref "C14") (pin "2") (pinfunction "2_2") (pintype "passive"))
      (node (ref "C15") (pin "2") (pinfunction "2_2") (pintype "passive"))
      (node (ref "F3") (pin "2") (pinfunction "2_2") (pintype "passive"))
      (node (ref "U4") (pin "12") (pinfunction "VISO_12") (pintype "bidirectional"))
    )
    (net (code "36") (name "Net-(U4-VSEL)") (class "Default")
      (node (ref "R25") (pin "1") (pinfunction "1_1") (pintype "passive"))
      (node (ref "R26") (pin "2") (pinfunction "2_2") (pintype "passive"))
      (node (ref "U4") (pin "13") (pinfunction "VSEL_13") (pintype "bidirectional"))
    )
    (net (code "37") (name "SCL1") (class "Default")
      (node (ref "IC2") (pin "13") (pinfunction "PA7_13") (pintype "bidirectional"))
      (node (ref "R9") (pin "1") (pinfunction "1_1") (pintype "passive"))
      (node (ref "U1") (pin "2") (pinfunction "SCL2_2") (pintype "bidirectional"))
    )
    (net (code "38") (name "SCL1_ISO") (class "Default")
      (node (ref "R1") (pin "1") (pinfunction "1_1") (pintype "passive"))
      (node (ref "R8") (pin "1") (pinfunction "1_1") (pintype "passive"))
      (node (ref "U1") (pin "19") (pinfunction "SCL1_19") (pintype "bidirectional"))
    )
    (net (code "39") (name "SCL2") (class "Default")
      (node (ref "IC2") (pin "29") (pinfunction "PB6_29") (pintype "bidirectional"))
      (node (ref "R29") (pin "1") (pinfunction "1_1") (pintype "passive"))
      (node (ref "U4") (pin "2") (pinfunction "SCL2_2") (pintype "bidirectional"))
    )
    (net (code "40") (name "SCL2_ISO") (class "Default")
      (node (ref "R23") (pin "1") (pinfunction "1_1") (pintype "passive"))
      (node (ref "R28") (pin "1") (pinfunction "1_1") (pintype "passive"))
      (node (ref "U4") (pin "19") (pinfunction "SCL1_19") (pintype "bidirectional"))
    )
    (net (code "41") (name "SDA1") (class "Default")
      (node (ref "IC2") (pin "27") (pinfunction "PB4_27") (pintype "bidirectional"))
      (node (ref "R10") (pin "1") (pinfunction "1_1") (pintype "passive"))
      (node (ref "U1") (pin "3") (pinfunction "SDA2_3") (pintype "bidirectional"))
    )
    (net (code "42") (name "SDA1_ISO") (class "Default")
      (node (ref "R2") (pin "1") (pinfunction "1_1") (pintype "passive"))
      (node (ref "R7") (pin "1") (pinfunction "1_1") (pintype "passive"))
      (node (ref "U1") (pin "18") (pinfunction "SDA1_18") (pintype "bidirectional"))
    )
    (net (code "43") (name "SDA2") (class "Default")
      (node (ref "IC2") (pin "30") (pinfunction "PB7_30") (pintype "bidirectional"))
      (node (ref "R30") (pin "1") (pinfunction "1_1") (pintype "passive"))
      (node (ref "U4") (pin "3") (pinfunction "SDA2_3") (pintype "bidirectional"))
    )
    (net (code "44") (name "SDA2_ISO") (class "Default")
      (node (ref "R24") (pin "1") (pinfunction "1_1") (pintype "passive"))
      (node (ref "R27") (pin "1") (pinfunction "1_1") (pintype "passive"))
      (node (ref "U4") (pin "18") (pinfunction "SDA1_18") (pintype "bidirectional"))
    )
    (net (code "45") (name "STATUS_BAD") (class "Default")
      (node (ref "IC2") (pin "26") (pinfunction "PB3_26") (pintype "bidirectional"))
      (node (ref "LED1") (pin "C1") (pinfunction "C_C1") (pintype "passive"))
    )
    (net (code "46") (name "STATUS_GOOD") (class "Default")
      (node (ref "IC2") (pin "25") (pinfunction "PA15_25") (pintype "bidirectional"))
      (node (ref "LED1") (pin "C2") (pinfunction "C_C2") (pintype "passive"))
    )
    (net (code "47") (name "SWCLK") (class "Default")
      (node (ref "IC2") (pin "24") (pinfunction "PA14_24") (pintype "bidirectional"))
      (node (ref "J3") (pin "4") (pinfunction "4_4") (pintype "passive"))
    )
    (net (code "48") (name "SWDIO") (class "Default")
      (node (ref "IC2") (pin "23") (pinfunction "PA13_23") (pintype "bidirectional"))
      (node (ref "J3") (pin "2") (pinfunction "2_2") (pintype "passive"))
    )
    (net (code "49") (name "USB_DM") (class "Default")
      (node (ref "IC2") (pin "21") (pinfunction "PA11_21") (pintype "bidirectional"))
      (node (ref "U3") (pin "6") (pinfunction "6_6") (pintype "bidirectional"))
    )
    (net (code "50") (name "USB_DP") (class "Default")
      (node (ref "IC2") (pin "22") (pinfunction "PA12_22") (pintype "bidirectional"))
      (node (ref "U3") (pin "4") (pinfunction "4_4") (pintype "bidirectional"))
    )
    (net (code "51") (name "VARIANT0") (class "Default")
      (node (ref "IC2") (pin "14") (pinfunction "PB0_14") (pintype "bidirectional"))
      (node (ref "R36") (pin "2") (pinfunction "2_2") (pintype "passive"))
    )
    (net (code "52") (name "VARIANT1") (class "Default")
      (node (ref "IC2") (pin "15") (pinfunction "PB1_15") (pintype "bidirectional"))
      (node (ref "R35") (pin "2") (pinfunction "2_2") (pintype "passive"))
    )
    (net (code "53") (name "VBUS") (class "Default")
      (node (ref "C1") (pin "1") (pinfunction "1_1") (pintype "passive"))
      (node (ref "C11") (pin "2") (pinfunction "2_2") (pintype "passive"))
      (node (ref "C12") (pin "2") (pinfunction "2_2") (pintype "passive"))
      (node (ref "C16") (pin "2") (pinfunction "2_2") (pintype "passive"))
      (node (ref "C17") (pin "2") (pinfunction "2_2") (pintype "passive"))
      (node (ref "C4") (pin "1") (pinfunction "1_1") (pintype "passive"))
      (node (ref "IC1") (pin "5") (pinfunction "S-_5") (pintype "input"))
      (node (ref "R19") (pin "2") (pinfunction "2_2") (pintype "passive"))
      (node (ref "R21") (pin "1") (pinfunction "1_1") (pintype "passive"))
      (node (ref "U1") (pin "9") (pinfunction "VIN_9") (pintype "bidirectional"))
      (node (ref "U2") (pin "1") (pinfunction "IN_1") (pintype "bidirectional"))
      (node (ref "U2") (pin "3") (pinfunction "ON/OFF_3") (pintype "bidirectional"))
      (node (ref "U4") (pin "9") (pinfunction "VIN_9") (pintype "bidirectional"))
    )
    (net (code "54") (name "VBUS_IN") (class "Default")
      (node (ref "F1") (pin "1") (pinfunction "1_1") (pintype "passive"))
      (node (ref "J2") (pin "A4/B9") (pinfunction "VBUS_A4/B9") (pintype "power_in"))
      (node (ref "J2") (pin "B4/A9") (pinfunction "VBUS_B4/A9") (pintype "power_in"))
      (node (ref "U3") (pin "5") (pinfunction "5_5") (pintype "passive"))
    )
    (net (code "55") (name "VCC") (class "Default")
      (node (ref "C10") (pin "1") (pinfunction "1_1") (pintype "passive"))
      (node (ref "C13") (pin "1") (pinfunction "1_1") (pintype "passive"))
      (node (ref "C19") (pin "2") (pinfunction "2_2") (pintype "passive"))
      (node (ref "C3") (pin "2") (pinfunction "2_2") (pintype "passive"))
      (node (ref "C5") (pin "1") (pinfunction "1_1") (pintype "passive"))
      (node (ref "C7") (pin "1") (pinfunction "1_1") (pintype "passive"))
      (node (ref "C9") (pin "1") (pinfunction "1_1") (pintype "passive"))
      (node (ref "IC2") (pin "1") (pinfunction "VDD_1") (pintype "bidirectional"))
      (node (ref "IC2") (pin "17") (pinfunction "VDD_17") (pintype "bidirectional"))
      (node (ref "IC2") (pin "5") (pinfunction "VDDA/VREF+_5") (pintype "bidirectional"))
      (node (ref "J3") (pin "1") (pinfunction "1_1") (pintype "passive"))
      (node (ref "R10") (pin "2") (pinfunction "2_2") (pintype "passive"))
      (node (ref "R12") (pin "2") (pinfunction "2_2") (pintype "passive"))
      (node (ref "R13") (pin "2") (pinfunction "2_2") (pintype "passive"))
      (node (ref "R17") (pin "2") (pinfunction "2_2") (pintype "passive"))
      (node (ref "R18") (pin "2") (pinfunction "2_2") (pintype "passive"))
      (node (ref "R29") (pin "2") (pinfunction "2_2") (pintype "passive"))
      (node (ref "R30") (pin "2") (pinfunction "2_2") (pintype "passive"))
      (node (ref "R33") (pin "2") (pinfunction "2_2") (pintype "passive"))
      (node (ref "R34") (pin "2") (pinfunction "2_2") (pintype "passive"))
      (node (ref "R9") (pin "2") (pinfunction "2_2") (pintype "passive"))
      (node (ref "U1") (pin "4") (pinfunction "VDDP_4") (pintype "bidirectional"))
      (node (ref "U2") (pin "5") (pinfunction "OUT_5") (pintype "bidirectional"))
      (node (ref "U4") (pin "4") (pinfunction "VDDP_4") (pintype "bidirectional"))
    )
    (net (code "56") (name "VDDISO1") (class "Default")
      (node (ref "C2") (pin "2") (pinfunction "2_2") (pintype "passive"))
      (node (ref "CON1") (pin "05") (pinfunction "05_05") (pintype "passive"))
      (node (ref "CON1") (pin "06") (pinfunction "06_06") (pintype "passive"))
      (node (ref "R7") (pin "2") (pinfunction "2_2") (pintype "passive"))
      (node (ref "R8") (pin "2") (pinfunction "2_2") (pintype "passive"))
      (node (ref "U1") (pin "17") (pinfunction "VDDISO_17") (pintype "bidirectional"))
    )
    (net (code "57") (name "VDDISO2") (class "Default")
      (node (ref "C18") (pin "2") (pinfunction "2_2") (pintype "passive"))
      (node (ref "CON2") (pin "05") (pinfunction "05_05") (pintype "passive"))
      (node (ref "CON2") (pin "06") (pinfunction "06_06") (pintype "passive"))
      (node (ref "R27") (pin "2") (pinfunction "2_2") (pintype "passive"))
      (node (ref "R28") (pin "2") (pinfunction "2_2") (pintype "passive"))
      (node (ref "U4") (pin "17") (pinfunction "VDDISO_17") (pintype "bidirectional"))
    )
    (net (code "58") (name "VISO1") (class "Default")
      (node (ref "CON1") (pin "01") (pinfunction "01_01") (pintype "passive"))
      (node (ref "CON1") (pin "02") (pinfunction "02_02") (pintype "passive"))
      (node (ref "F2") (pin "1") (pinfunction "1_1") (pintype "passive"))
      (node (ref "R15") (pin "2") (pinfunction "2_2") (pintype "passive"))
      (node (ref "R16") (pin "2") (pinfunction "2_2") (pintype "passive"))
      (node (ref "R5") (pin "2") (pinfunction "2_2") (pintype "passive"))
    )
    (net (code "59") (name "VISO2") (class "Default")
      (node (ref "CON2") (pin "01") (pinfunction "01_01") (pintype "passive"))
      (node (ref "CON2") (pin "02") (pinfunction "02_02") (pintype "passive"))
      (node (ref "F3") (pin "1") (pinfunction "1_1") (pintype "passive"))
      (node (ref "R25") (pin "2") (pinfunction "2_2") (pintype "passive"))
      (node (ref "R31") (pin "2") (pinfunction "2_2") (pintype "passive"))
      (node (ref "R32") (pin "2") (pinfunction "2_2") (pintype "passive"))
    )
    (net (code "60") (name "unconnected-(IC2-PA2-Pad8)") (class "Default")
      (node (ref "IC2") (pin "8") (pinfunction "PA2_8") (pintype "bidirectional"))
    )
    (net (code "61") (name "unconnected-(IC2-PA6-Pad12)") (class "Default")
      (node (ref "IC2") (pin "12") (pinfunction "PA6_12") (pintype "bidirectional"))
    )
    (net (code "62") (name "unconnected-(IC2-PA8-Pad18)") (class "Default")
      (node (ref "IC2") (pin "18") (pinfunction "PA8_18") (pintype "bidirectional"))
    )
    (net (code "63") (name "unconnected-(IC2-PA9-Pad19)") (class "Default")
      (node (ref "IC2") (pin "19") (pinfunction "PA9_19") (pintype "bidirectional"))
    )
    (net (code "64") (name "unconnected-(IC2-PA10-Pad20)") (class "Default")
      (node (ref "IC2") (pin "20") (pinfunction "PA10_20") (pintype "bidirectional"))
    )
    (net (code "65") (name "unconnected-(IC2-PB5-Pad28)") (class "Default")
      (node (ref "IC2") (pin "28") (pinfunction "PB5_28") (pintype "bidirectional"))
    )
    (net (code "66") (name "unconnected-(J2-SBU1-PadA8)") (class "Default")
      (node (ref "J2") (pin "A8") (pinfunction "SBU1_A8") (pintype "bidirectional"))
    )
    (net (code "67") (name "unconnected-(J2-SBU2-PadB8)") (class "Default")
      (node (ref "J2") (pin "B8") (pinfunction "SBU2_B8") (pintype "bidirectional"))
    )
    (net (code "68") (name "unconnected-(J3-Pad6)") (class "Default")
      (node (ref "J3") (pin "6") (pinfunction "6_6") (pintype "passive"))
    )
    (net (code "69") (name "unconnected-(J3-Pad7)") (class "Default")
      (node (ref "J3") (pin "7") (pinfunction "7_7") (pintype "passive"))
    )
    (net (code "70") (name "unconnected-(J3-Pad8)") (class "Default")
      (node (ref "J3") (pin "8") (pinfunction "8_8") (pintype "passive"))
    )
    (net (code "71") (name "unconnected-(J3-Pad9)") (class "Default")
      (node (ref "J3") (pin "9") (pinfunction "9_9") (pintype "passive"))
    )
    (net (code "72") (name "~{NRST}") (class "Default")
      (node (ref "IC2") (pin "4") (pinfunction "~{NRST}_4") (pintype "bidirectional"))
      (node (ref "J3") (pin "10") (pinfunction "10_10") (pintype "passive"))
    )
  )
)
